# untitled.net
KiCad netlist of a schematic drawn in EAGLE
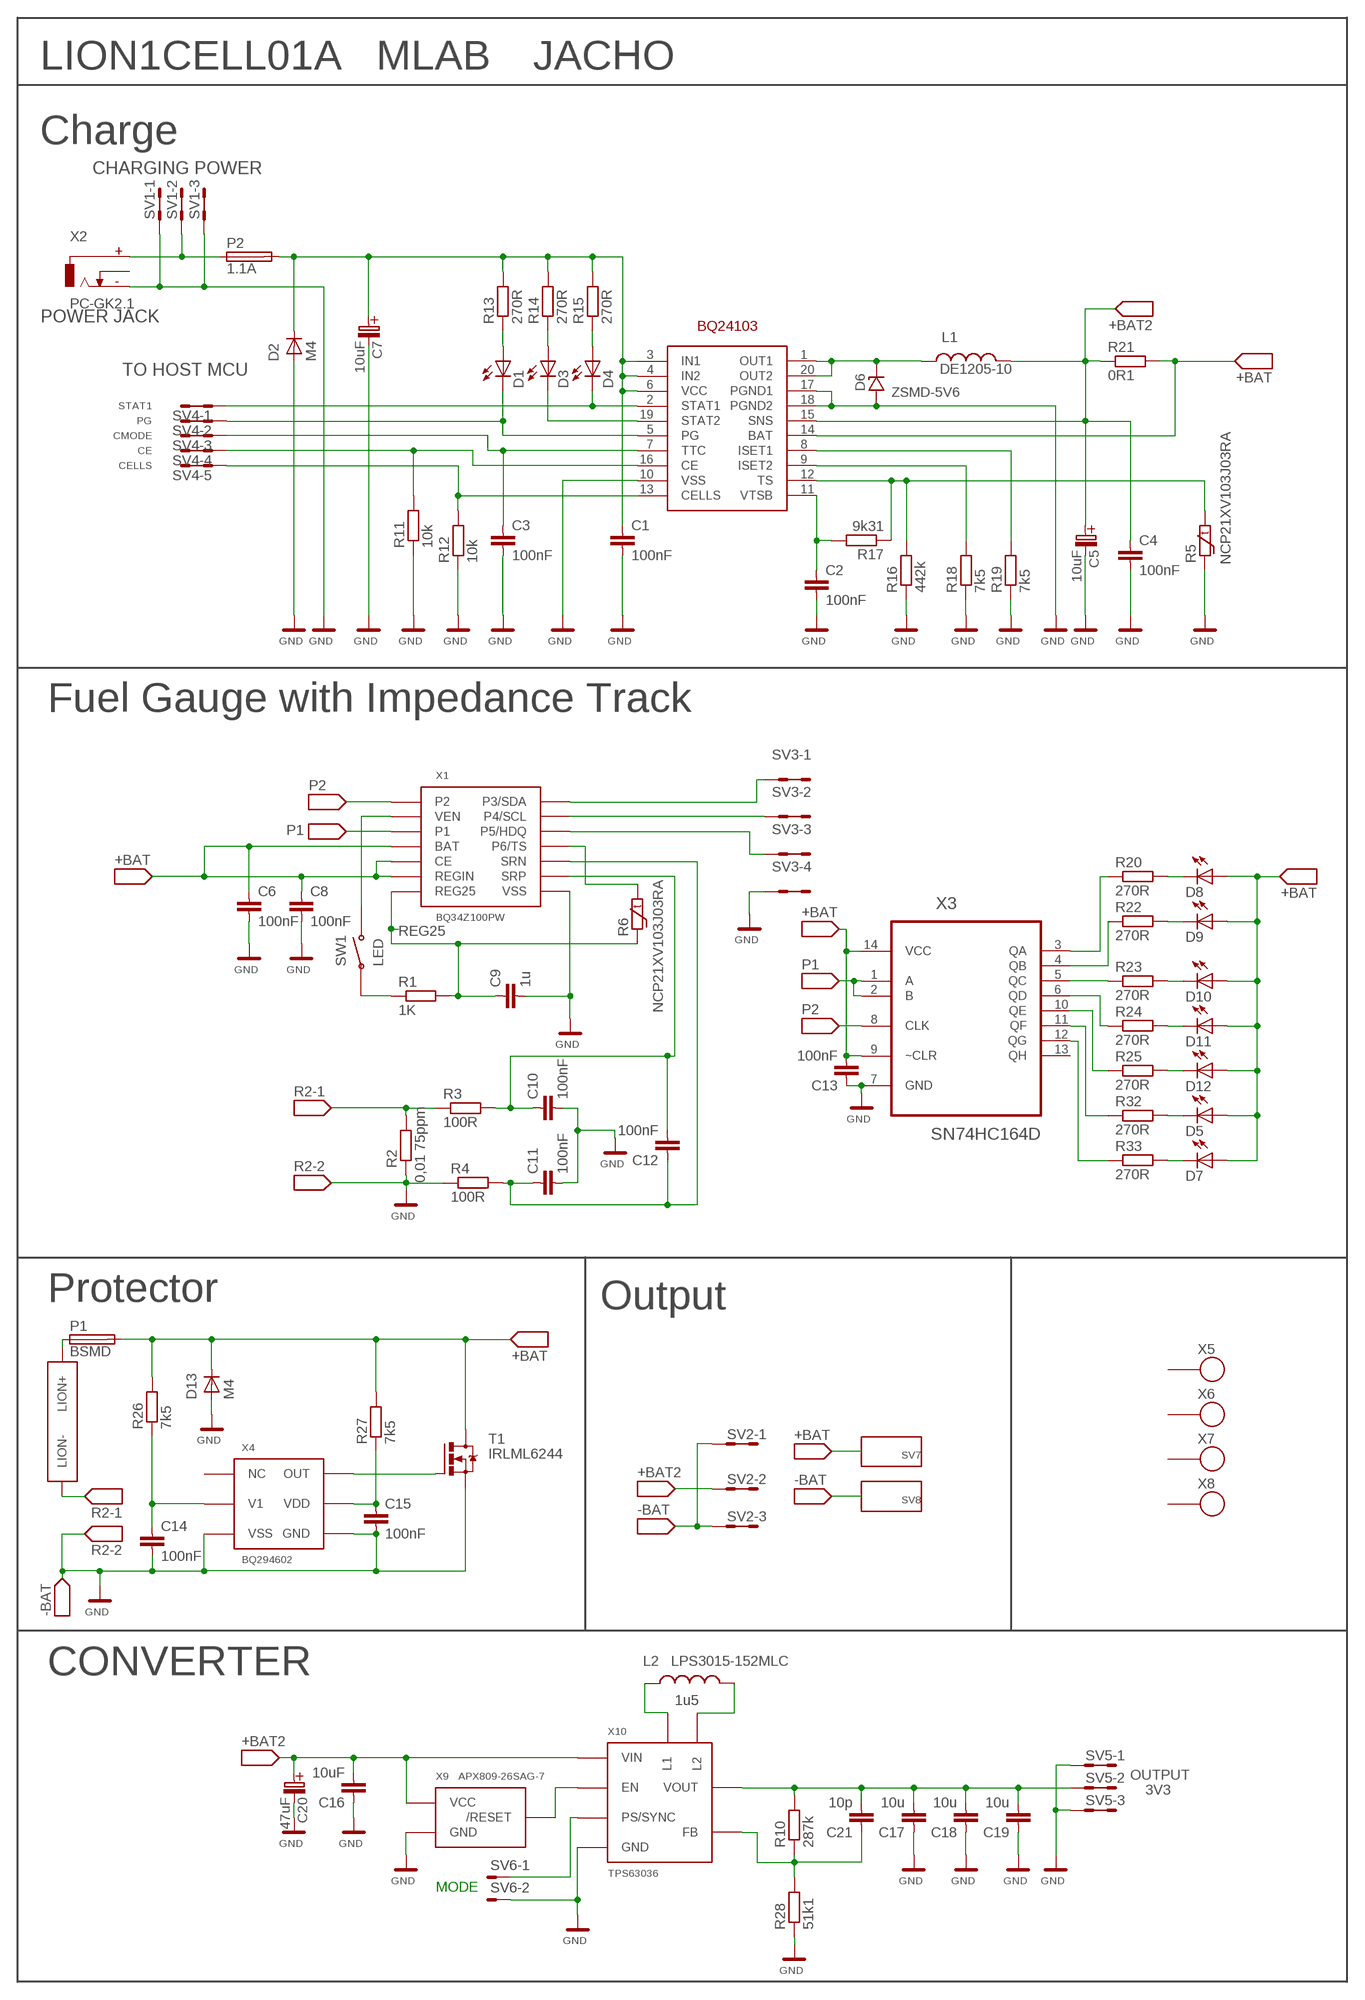
[diagram p0: schematic, sheet 1]

(export (version "E")
  (design (tool "Eeschema 10.0.6"))
  (components
    (comp (ref "C1")
      (value "100nF")
      (footprint "eagle-import:C0805")
      (libsource (lib "eagle-import") (part "C0805"))
    )
    (comp (ref "C2")
      (value "100nF")
      (footprint "eagle-import:C0805")
      (libsource (lib "eagle-import") (part "C0805"))
    )
    (comp (ref "C3")
      (value "100nF")
      (footprint "eagle-import:C0805")
      (libsource (lib "eagle-import") (part "C0805"))
    )
    (comp (ref "C4")
      (value "100nF")
      (footprint "eagle-import:C0805")
      (libsource (lib "eagle-import") (part "C0805"))
    )
    (comp (ref "C5") (value "10uF") (footprint "eagle-import:B") (libsource (lib "eagle-import") (part "B")))
    (comp (ref "C6")
      (value "100nF")
      (footprint "eagle-import:C0805")
      (libsource (lib "eagle-import") (part "C0805"))
    )
    (comp (ref "C7") (value "10uF") (footprint "eagle-import:B") (libsource (lib "eagle-import") (part "B")))
    (comp (ref "C8")
      (value "100nF")
      (footprint "eagle-import:C0805")
      (libsource (lib "eagle-import") (part "C0805"))
    )
    (comp (ref "C9")
      (value "1u")
      (footprint "eagle-import:C0805")
      (libsource (lib "eagle-import") (part "C0805"))
    )
    (comp (ref "C10")
      (value "100nF")
      (footprint "eagle-import:C0805")
      (libsource (lib "eagle-import") (part "C0805"))
    )
    (comp (ref "C11")
      (value "100nF")
      (footprint "eagle-import:C0805")
      (libsource (lib "eagle-import") (part "C0805"))
    )
    (comp (ref "C12")
      (value "100nF")
      (footprint "eagle-import:C0805")
      (libsource (lib "eagle-import") (part "C0805"))
    )
    (comp (ref "C13")
      (value "100nF")
      (footprint "eagle-import:C0805")
      (libsource (lib "eagle-import") (part "C0805"))
    )
    (comp (ref "C14")
      (value "100nF")
      (footprint "eagle-import:C0805")
      (libsource (lib "eagle-import") (part "C0805"))
    )
    (comp (ref "C15")
      (value "100nF")
      (footprint "eagle-import:C0805")
      (libsource (lib "eagle-import") (part "C0805"))
    )
    (comp (ref "C16")
      (value "10uF")
      (footprint "eagle-import:C0805")
      (libsource (lib "eagle-import") (part "C0805"))
    )
    (comp (ref "C17")
      (value "10u")
      (footprint "eagle-import:C0805")
      (libsource (lib "eagle-import") (part "C0805"))
    )
    (comp (ref "C18")
      (value "10u")
      (footprint "eagle-import:C0805")
      (libsource (lib "eagle-import") (part "C0805"))
    )
    (comp (ref "C19")
      (value "10u")
      (footprint "eagle-import:C0805")
      (libsource (lib "eagle-import") (part "C0805"))
    )
    (comp (ref "C20") (value "47uF") (footprint "eagle-import:B") (libsource (lib "eagle-import") (part "B")))
    (comp (ref "C21")
      (value "10p")
      (footprint "eagle-import:0603")
      (libsource (lib "eagle-import") (part "C0603"))
    )
    (comp (ref "D1")
      (value "LED1206_2")
      (footprint "eagle-import:1206_2")
      (libsource (lib "eagle-import") (part "LED1206_2"))
    )
    (comp (ref "D2")
      (value "M4")
      (footprint "eagle-import:SMB")
      (libsource (lib "eagle-import") (part "D-OB."))
    )
    (comp (ref "D3")
      (value "LED1206_2")
      (footprint "eagle-import:1206_2")
      (libsource (lib "eagle-import") (part "LED1206_2"))
    )
    (comp (ref "D4")
      (value "LED1206_2")
      (footprint "eagle-import:1206_2")
      (libsource (lib "eagle-import") (part "LED1206_2"))
    )
    (comp (ref "D5")
      (value "LED1206_2")
      (footprint "eagle-import:1206_2")
      (libsource (lib "eagle-import") (part "LED1206_2"))
    )
    (comp (ref "D6")
      (value "ZSMD-5V6")
      (footprint "eagle-import:MINIMELF")
      (libsource (lib "eagle-import") (part "D-ZENEROVA"))
    )
    (comp (ref "D7")
      (value "LED1206_2")
      (footprint "eagle-import:1206_2")
      (libsource (lib "eagle-import") (part "LED1206_2"))
    )
    (comp (ref "D8")
      (value "LED1206_2")
      (footprint "eagle-import:1206_2")
      (libsource (lib "eagle-import") (part "LED1206_2"))
    )
    (comp (ref "D9")
      (value "LED1206_2")
      (footprint "eagle-import:1206_2")
      (libsource (lib "eagle-import") (part "LED1206_2"))
    )
    (comp (ref "D10")
      (value "LED1206_2")
      (footprint "eagle-import:1206_2")
      (libsource (lib "eagle-import") (part "LED1206_2"))
    )
    (comp (ref "D11")
      (value "LED1206_2")
      (footprint "eagle-import:1206_2")
      (libsource (lib "eagle-import") (part "LED1206_2"))
    )
    (comp (ref "D12")
      (value "LED1206_2")
      (footprint "eagle-import:1206_2")
      (libsource (lib "eagle-import") (part "LED1206_2"))
    )
    (comp (ref "D13")
      (value "M4")
      (footprint "eagle-import:SMA")
      (libsource (lib "eagle-import") (part "D-OB.SMA"))
    )
    (comp (ref "L1")
      (value "DE1205-10")
      (footprint "eagle-import:DE1205-10")
      (libsource (lib "eagle-import") (part "DE1205-10"))
    )
    (comp (ref "L2")
      (value "LPS3015-152MLC")
      (footprint "eagle-import:LPS3015")
      (libsource (lib "eagle-import") (part "LPS3015"))
    )
    (comp (ref "P1")
      (value "BSMD")
      (footprint "eagle-import:2410")
      (libsource (lib "eagle-import") (part "POJISTKA2410"))
    )
    (comp (ref "P2")
      (value "1.1A")
      (footprint "eagle-import:1812")
      (libsource (lib "eagle-import") (part "POJISTKA_1812"))
    )
    (comp (ref "R1")
      (value "1K")
      (footprint "eagle-import:0805")
      (libsource (lib "eagle-import") (part "R0805"))
    )
    (comp (ref "R2")
      (value "0,01 75ppm")
      (footprint "eagle-import:0805")
      (libsource (lib "eagle-import") (part "R0805"))
    )
    (comp (ref "R3")
      (value "100R")
      (footprint "eagle-import:0805")
      (libsource (lib "eagle-import") (part "R0805"))
    )
    (comp (ref "R4")
      (value "100R")
      (footprint "eagle-import:0805")
      (libsource (lib "eagle-import") (part "R0805"))
    )
    (comp (ref "R5")
      (value "NCP21XV103J03RA")
      (footprint "eagle-import:0805")
      (libsource (lib "eagle-import") (part "TERMISTOR0805"))
    )
    (comp (ref "R6")
      (value "NCP21XV103J03RA")
      (footprint "eagle-import:0805")
      (libsource (lib "eagle-import") (part "TERMISTOR0805"))
    )
    (comp (ref "R10")
      (value "287k")
      (footprint "eagle-import:0603")
      (libsource (lib "eagle-import") (part "R0603"))
    )
    (comp (ref "R11")
      (value "10k")
      (footprint "eagle-import:0805")
      (libsource (lib "eagle-import") (part "R0805"))
    )
    (comp (ref "R12")
      (value "10k")
      (footprint "eagle-import:0805")
      (libsource (lib "eagle-import") (part "R0805"))
    )
    (comp (ref "R13")
      (value "270R")
      (footprint "eagle-import:0805")
      (libsource (lib "eagle-import") (part "R0805"))
    )
    (comp (ref "R14")
      (value "270R")
      (footprint "eagle-import:0805")
      (libsource (lib "eagle-import") (part "R0805"))
    )
    (comp (ref "R15")
      (value "270R")
      (footprint "eagle-import:0805")
      (libsource (lib "eagle-import") (part "R0805"))
    )
    (comp (ref "R16")
      (value "442k")
      (footprint "eagle-import:0805")
      (libsource (lib "eagle-import") (part "R0805"))
    )
    (comp (ref "R17")
      (value "9k31")
      (footprint "eagle-import:0805")
      (libsource (lib "eagle-import") (part "R0805"))
    )
    (comp (ref "R18")
      (value "7k5")
      (footprint "eagle-import:0805")
      (libsource (lib "eagle-import") (part "R0805"))
    )
    (comp (ref "R19")
      (value "7k5")
      (footprint "eagle-import:0805")
      (libsource (lib "eagle-import") (part "R0805"))
    )
    (comp (ref "R20")
      (value "270R")
      (footprint "eagle-import:0805")
      (libsource (lib "eagle-import") (part "R0805"))
    )
    (comp (ref "R21")
      (value "0R1")
      (footprint "eagle-import:R2512")
      (libsource (lib "eagle-import") (part "R-EU_R2512"))
    )
    (comp (ref "R22")
      (value "270R")
      (footprint "eagle-import:0805")
      (libsource (lib "eagle-import") (part "R0805"))
    )
    (comp (ref "R23")
      (value "270R")
      (footprint "eagle-import:0805")
      (libsource (lib "eagle-import") (part "R0805"))
    )
    (comp (ref "R24")
      (value "270R")
      (footprint "eagle-import:0805")
      (libsource (lib "eagle-import") (part "R0805"))
    )
    (comp (ref "R25")
      (value "270R")
      (footprint "eagle-import:0805")
      (libsource (lib "eagle-import") (part "R0805"))
    )
    (comp (ref "R26")
      (value "7k5")
      (footprint "eagle-import:0805")
      (libsource (lib "eagle-import") (part "R0805"))
    )
    (comp (ref "R27")
      (value "7k5")
      (footprint "eagle-import:0805")
      (libsource (lib "eagle-import") (part "R0805"))
    )
    (comp (ref "R28")
      (value "51k1")
      (footprint "eagle-import:0603")
      (libsource (lib "eagle-import") (part "R0603"))
    )
    (comp (ref "R32")
      (value "270R")
      (footprint "eagle-import:0805")
      (libsource (lib "eagle-import") (part "R0805"))
    )
    (comp (ref "R33")
      (value "270R")
      (footprint "eagle-import:0805")
      (libsource (lib "eagle-import") (part "R0805"))
    )
    (comp (ref "SV1")
      (value "MA03-2")
      (footprint "eagle-import:MA03-2")
      (libsource (lib "eagle-import") (part "MA03-2"))
    )
    (comp (ref "SV2")
      (value "MA03-2")
      (footprint "eagle-import:MA03-2")
      (libsource (lib "eagle-import") (part "MA03-2"))
    )
    (comp (ref "SV3")
      (value "MA04-2")
      (footprint "eagle-import:MA04-2")
      (libsource (lib "eagle-import") (part "MA04-2"))
    )
    (comp (ref "SV4")
      (value "MA05-2")
      (footprint "eagle-import:MA05-2")
      (libsource (lib "eagle-import") (part "MA05-2"))
    )
    (comp (ref "SV5")
      (value "MA03-2")
      (footprint "eagle-import:MA03-2")
      (libsource (lib "eagle-import") (part "MA03-2"))
    )
    (comp (ref "SV6")
      (value "MA02-1")
      (footprint "eagle-import:MA02-1")
      (libsource (lib "eagle-import") (part "MA02-1"))
    )
    (comp (ref "SV7")
      (value "WAGO256")
      (footprint "eagle-import:WAGO256")
      (libsource (lib "eagle-import") (part "WAGO256"))
    )
    (comp (ref "SV8")
      (value "WAGO256")
      (footprint "eagle-import:WAGO256")
      (libsource (lib "eagle-import") (part "WAGO256"))
    )
    (comp (ref "SW1")
      (value "TACT-64K")
      (footprint "eagle-import:TACT-64K")
      (libsource (lib "eagle-import") (part "TACT-64K"))
    )
    (comp (ref "T1")
      (value "IRLML6244")
      (footprint "eagle-import:SOT23")
      (libsource (lib "eagle-import") (part "IRLML6244TRPBF"))
    )
    (comp (ref "U$2")
      (value "LION1")
      (footprint "eagle-import:LION1")
      (libsource (lib "eagle-import") (part "LION1"))
    )
    (comp (ref "U1")
      (value "BQ24103")
      (footprint "eagle-import:RHL_R-VQFN-N20")
      (libsource (lib "eagle-import") (part "BQ24103"))
    )
    (comp (ref "X1")
      (value "BQ34Z100PW")
      (footprint "eagle-import:TSSOP14")
      (libsource (lib "eagle-import") (part "BQ34Z100PW"))
    )
    (comp (ref "X2")
      (value "DC2.1MM")
      (footprint "eagle-import:DC2.1MM")
      (libsource (lib "eagle-import") (part "DC2.1MM"))
    )
    (comp (ref "X3")
      (value "SN74HC164D")
      (footprint "eagle-import:SOIC127P600X175-14N")
      (libsource (lib "eagle-import") (part "SN74HC164D"))
    )
    (comp (ref "X4")
      (value "BQ294602")
      (footprint "eagle-import:SON_N6")
      (libsource (lib "eagle-import") (part "BQ294602"))
    )
    (comp (ref "X5")
      (value "SROUB3M")
      (footprint "eagle-import:SROUB3M")
      (libsource (lib "eagle-import") (part "SROUB3M"))
    )
    (comp (ref "X6")
      (value "SROUB3M")
      (footprint "eagle-import:SROUB3M")
      (libsource (lib "eagle-import") (part "SROUB3M"))
    )
    (comp (ref "X7")
      (value "SROUB3M")
      (footprint "eagle-import:SROUB3M")
      (libsource (lib "eagle-import") (part "SROUB3M"))
    )
    (comp (ref "X8")
      (value "SROUB3M")
      (footprint "eagle-import:SROUB3M")
      (libsource (lib "eagle-import") (part "SROUB3M"))
    )
    (comp (ref "X9")
      (value "APX809-26SAG-7")
      (footprint "eagle-import:SOT23")
      (libsource (lib "eagle-import") (part "APX809-26SA"))
    )
    (comp (ref "X10")
      (value "TPS63036")
      (footprint "eagle-import:DSBGA8")
      (libsource (lib "eagle-import") (part "TPS63036"))
    )
  )
  (nets
    (net (code "1") (name "/+BAT") (class "Default")
      (node (ref "C13") (pin "2") (pinfunction "2_2") (pintype "passive"))
      (node (ref "C6") (pin "1") (pinfunction "1_1") (pintype "passive"))
      (node (ref "C8") (pin "1") (pinfunction "1_1") (pintype "passive"))
      (node (ref "D10") (pin "A") (pinfunction "A_A") (pintype "passive"))
      (node (ref "D11") (pin "A") (pinfunction "A_A") (pintype "passive"))
      (node (ref "D12") (pin "A") (pinfunction "A_A") (pintype "passive"))
      (node (ref "D13") (pin "K") (pinfunction "C_K") (pintype "passive"))
      (node (ref "D5") (pin "A") (pinfunction "A_A") (pintype "passive"))
      (node (ref "D7") (pin "A") (pinfunction "A_A") (pintype "passive"))
      (node (ref "D8") (pin "A") (pinfunction "A_A") (pintype "passive"))
      (node (ref "D9") (pin "A") (pinfunction "A_A") (pintype "passive"))
      (node (ref "P1") (pin "2") (pinfunction "2_2") (pintype "passive"))
      (node (ref "R21") (pin "2") (pinfunction "2_2") (pintype "passive"))
      (node (ref "R26") (pin "2") (pinfunction "2_2") (pintype "passive"))
      (node (ref "R27") (pin "2") (pinfunction "2_2") (pintype "passive"))
      (node (ref "SV7") (pin "1") (pinfunction "P$1_1") (pintype "passive"))
      (node (ref "SV7") (pin "A1") (pinfunction "P$1_A1") (pintype "passive"))
      (node (ref "T1") (pin "3") (pinfunction "D_3") (pintype "passive"))
      (node (ref "U1") (pin "14") (pinfunction "BAT_14") (pintype "bidirectional"))
      (node (ref "X1") (pin "4") (pinfunction "BAT_4") (pintype "bidirectional"))
      (node (ref "X1") (pin "5") (pinfunction "CE_5") (pintype "bidirectional"))
      (node (ref "X1") (pin "6") (pinfunction "REGIN_6") (pintype "bidirectional"))
      (node (ref "X3") (pin "14") (pinfunction "VCC_14") (pintype "power_in"))
      (node (ref "X3") (pin "9") (pinfunction "~{CLR}_9") (pintype "input"))
    )
    (net (code "2") (name "/+BAT2") (class "Default")
      (node (ref "C16") (pin "2") (pinfunction "2_2") (pintype "passive"))
      (node (ref "C20") (pin "+") (pinfunction "C_EL+_+") (pintype "passive"))
      (node (ref "C4") (pin "1") (pinfunction "1_1") (pintype "passive"))
      (node (ref "C5") (pin "+") (pinfunction "C_EL+_+") (pintype "passive"))
      (node (ref "L1") (pin "P$2") (pinfunction "2_P$2") (pintype "passive"))
      (node (ref "R21") (pin "1") (pinfunction "1_1") (pintype "passive"))
      (node (ref "SV2") (pin "3") (pinfunction "K_3") (pintype "passive"))
      (node (ref "SV2") (pin "4") (pinfunction "K_4") (pintype "passive"))
      (node (ref "U1") (pin "15") (pinfunction "SNS_15") (pintype "bidirectional"))
      (node (ref "X10") (pin "A1") (pinfunction "VIN_A1") (pintype "input"))
      (node (ref "X9") (pin "3") (pinfunction "VCC_3") (pintype "input"))
    )
    (net (code "3") (name "/P1") (class "Default")
      (node (ref "X1") (pin "3") (pinfunction "P1_3") (pintype "bidirectional"))
      (node (ref "X3") (pin "1") (pinfunction "A_1") (pintype "input"))
      (node (ref "X3") (pin "2") (pinfunction "B_2") (pintype "input"))
    )
    (net (code "4") (name "/P2") (class "Default")
      (node (ref "X1") (pin "1") (pinfunction "P2_1") (pintype "bidirectional"))
      (node (ref "X3") (pin "8") (pinfunction "CLK_8") (pintype "input"))
    )
    (net (code "5") (name "/R2") (class "Default")
      (node (ref "R2") (pin "2") (pinfunction "2_2") (pintype "passive"))
      (node (ref "R3") (pin "1") (pinfunction "1_1") (pintype "passive"))
      (node (ref "U$2") (pin "-") (pinfunction "LION-_-") (pintype "bidirectional"))
      (node (ref "U$2") (pin "-1") (pinfunction "LION-_-1") (pintype "bidirectional"))
    )
    (net (code "6") (name "GND") (class "Default")
      (node (ref "C1") (pin "2") (pinfunction "2_2") (pintype "passive"))
      (node (ref "C10") (pin "2") (pinfunction "2_2") (pintype "passive"))
      (node (ref "C11") (pin "2") (pinfunction "2_2") (pintype "passive"))
      (node (ref "C13") (pin "1") (pinfunction "1_1") (pintype "passive"))
      (node (ref "C14") (pin "2") (pinfunction "2_2") (pintype "passive"))
      (node (ref "C15") (pin "2") (pinfunction "2_2") (pintype "passive"))
      (node (ref "C16") (pin "1") (pinfunction "1_1") (pintype "passive"))
      (node (ref "C17") (pin "1") (pinfunction "1_1") (pintype "passive"))
      (node (ref "C18") (pin "1") (pinfunction "1_1") (pintype "passive"))
      (node (ref "C19") (pin "1") (pinfunction "1_1") (pintype "passive"))
      (node (ref "C2") (pin "2") (pinfunction "2_2") (pintype "passive"))
      (node (ref "C20") (pin "-") (pinfunction "C_EL-_-") (pintype "passive"))
      (node (ref "C3") (pin "2") (pinfunction "2_2") (pintype "passive"))
      (node (ref "C4") (pin "2") (pinfunction "2_2") (pintype "passive"))
      (node (ref "C5") (pin "-") (pinfunction "C_EL-_-") (pintype "passive"))
      (node (ref "C6") (pin "2") (pinfunction "2_2") (pintype "passive"))
      (node (ref "C7") (pin "-") (pinfunction "C_EL-_-") (pintype "passive"))
      (node (ref "C8") (pin "2") (pinfunction "2_2") (pintype "passive"))
      (node (ref "C9") (pin "2") (pinfunction "2_2") (pintype "passive"))
      (node (ref "D13") (pin "A") (pinfunction "A_A") (pintype "passive"))
      (node (ref "D2") (pin "A") (pinfunction "A_A") (pintype "passive"))
      (node (ref "D6") (pin "A") (pinfunction "A_A") (pintype "passive"))
      (node (ref "R11") (pin "1") (pinfunction "1_1") (pintype "passive"))
      (node (ref "R12") (pin "1") (pinfunction "1_1") (pintype "passive"))
      (node (ref "R16") (pin "1") (pinfunction "1_1") (pintype "passive"))
      (node (ref "R18") (pin "1") (pinfunction "1_1") (pintype "passive"))
      (node (ref "R19") (pin "1") (pinfunction "1_1") (pintype "passive"))
      (node (ref "R2") (pin "1") (pinfunction "1_1") (pintype "passive"))
      (node (ref "R28") (pin "1") (pinfunction "1_1") (pintype "passive"))
      (node (ref "R4") (pin "1") (pinfunction "1_1") (pintype "passive"))
      (node (ref "R5") (pin "1") (pinfunction "1_1") (pintype "passive"))
      (node (ref "SV1") (pin "1") (pinfunction "K_1") (pintype "passive"))
      (node (ref "SV1") (pin "2") (pinfunction "K_2") (pintype "passive"))
      (node (ref "SV1") (pin "5") (pinfunction "K_5") (pintype "passive"))
      (node (ref "SV1") (pin "6") (pinfunction "K_6") (pintype "passive"))
      (node (ref "SV2") (pin "1") (pinfunction "K_1") (pintype "passive"))
      (node (ref "SV2") (pin "2") (pinfunction "K_2") (pintype "passive"))
      (node (ref "SV2") (pin "5") (pinfunction "K_5") (pintype "passive"))
      (node (ref "SV2") (pin "6") (pinfunction "K_6") (pintype "passive"))
      (node (ref "SV3") (pin "7") (pinfunction "K_7") (pintype "passive"))
      (node (ref "SV3") (pin "8") (pinfunction "K_8") (pintype "passive"))
      (node (ref "SV5") (pin "1") (pinfunction "K_1") (pintype "passive"))
      (node (ref "SV5") (pin "2") (pinfunction "K_2") (pintype "passive"))
      (node (ref "SV5") (pin "5") (pinfunction "K_5") (pintype "passive"))
      (node (ref "SV5") (pin "6") (pinfunction "K_6") (pintype "passive"))
      (node (ref "SV6") (pin "2") (pinfunction "P$1_2") (pintype "passive"))
      (node (ref "SV8") (pin "1") (pinfunction "P$1_1") (pintype "passive"))
      (node (ref "SV8") (pin "A1") (pinfunction "P$1_A1") (pintype "passive"))
      (node (ref "T1") (pin "2") (pinfunction "S_2") (pintype "passive"))
      (node (ref "U1") (pin "10") (pinfunction "VSS_10") (pintype "bidirectional"))
      (node (ref "U1") (pin "17") (pinfunction "PGND1_17") (pintype "bidirectional"))
      (node (ref "U1") (pin "18") (pinfunction "PGND2_18") (pintype "bidirectional"))
      (node (ref "X1") (pin "8") (pinfunction "VSS_8") (pintype "bidirectional"))
      (node (ref "X10") (pin "C2") (pinfunction "GND_C2") (pintype "passive"))
      (node (ref "X2") (pin "GND") (pinfunction "-_GND") (pintype "passive"))
      (node (ref "X3") (pin "7") (pinfunction "GND_7") (pintype "passive"))
      (node (ref "X4") (pin "3") (pinfunction "VSS_3") (pintype "bidirectional"))
      (node (ref "X4") (pin "4") (pinfunction "VSS_4") (pintype "bidirectional"))
      (node (ref "X4") (pin "7") (pinfunction "GND_7") (pintype "bidirectional"))
      (node (ref "X9") (pin "1") (pinfunction "GND_1") (pintype "passive"))
    )
    (net (code "7") (name "Net-(C7-C_EL+)") (class "Default")
      (node (ref "C1") (pin "1") (pinfunction "1_1") (pintype "passive"))
      (node (ref "C7") (pin "+") (pinfunction "C_EL+_+") (pintype "passive"))
      (node (ref "D2") (pin "K") (pinfunction "C_K") (pintype "passive"))
      (node (ref "P2") (pin "2") (pinfunction "2_2") (pintype "passive"))
      (node (ref "R13") (pin "2") (pinfunction "2_2") (pintype "passive"))
      (node (ref "R14") (pin "2") (pinfunction "2_2") (pintype "passive"))
      (node (ref "R15") (pin "2") (pinfunction "2_2") (pintype "passive"))
      (node (ref "U1") (pin "3") (pinfunction "IN1_3") (pintype "bidirectional"))
      (node (ref "U1") (pin "4") (pinfunction "IN2_4") (pintype "bidirectional"))
      (node (ref "U1") (pin "6") (pinfunction "VCC_6") (pintype "bidirectional"))
    )
    (net (code "8") (name "Net-(D1-C)") (class "Default")
      (node (ref "D1") (pin "K") (pinfunction "C_K") (pintype "passive"))
      (node (ref "SV4") (pin "3") (pinfunction "K_3") (pintype "passive"))
      (node (ref "SV4") (pin "4") (pinfunction "K_4") (pintype "passive"))
      (node (ref "U1") (pin "5") (pinfunction "PG_5") (pintype "bidirectional"))
    )
    (net (code "9") (name "Net-(D1-PadA)") (class "Default")
      (node (ref "D1") (pin "A") (pinfunction "A_A") (pintype "passive"))
      (node (ref "R13") (pin "1") (pinfunction "1_1") (pintype "passive"))
    )
    (net (code "10") (name "Net-(D3-C)") (class "Default")
      (node (ref "D3") (pin "K") (pinfunction "C_K") (pintype "passive"))
      (node (ref "U1") (pin "19") (pinfunction "STAT2_19") (pintype "bidirectional"))
    )
    (net (code "11") (name "Net-(D3-PadA)") (class "Default")
      (node (ref "D3") (pin "A") (pinfunction "A_A") (pintype "passive"))
      (node (ref "R14") (pin "1") (pinfunction "1_1") (pintype "passive"))
    )
    (net (code "12") (name "Net-(D4-C)") (class "Default")
      (node (ref "D4") (pin "K") (pinfunction "C_K") (pintype "passive"))
      (node (ref "SV4") (pin "1") (pinfunction "K_1") (pintype "passive"))
      (node (ref "SV4") (pin "2") (pinfunction "K_2") (pintype "passive"))
      (node (ref "U1") (pin "2") (pinfunction "STAT1_2") (pintype "bidirectional"))
    )
    (net (code "13") (name "Net-(D4-PadA)") (class "Default")
      (node (ref "D4") (pin "A") (pinfunction "A_A") (pintype "passive"))
      (node (ref "R15") (pin "1") (pinfunction "1_1") (pintype "passive"))
    )
    (net (code "14") (name "Net-(D5-C)") (class "Default")
      (node (ref "D5") (pin "K") (pinfunction "C_K") (pintype "passive"))
      (node (ref "R32") (pin "2") (pinfunction "2_2") (pintype "passive"))
    )
    (net (code "15") (name "Net-(D6-K)") (class "Default")
      (node (ref "D6") (pin "C") (pinfunction "K_C") (pintype "passive"))
      (node (ref "L1") (pin "P$1") (pinfunction "1_P$1") (pintype "passive"))
      (node (ref "U1") (pin "1") (pinfunction "OUT1_1") (pintype "bidirectional"))
      (node (ref "U1") (pin "20") (pinfunction "OUT2_20") (pintype "bidirectional"))
    )
    (net (code "16") (name "Net-(D7-C)") (class "Default")
      (node (ref "D7") (pin "K") (pinfunction "C_K") (pintype "passive"))
      (node (ref "R33") (pin "2") (pinfunction "2_2") (pintype "passive"))
    )
    (net (code "17") (name "Net-(D8-C)") (class "Default")
      (node (ref "D8") (pin "K") (pinfunction "C_K") (pintype "passive"))
      (node (ref "R20") (pin "2") (pinfunction "2_2") (pintype "passive"))
    )
    (net (code "18") (name "Net-(D9-C)") (class "Default")
      (node (ref "D9") (pin "K") (pinfunction "C_K") (pintype "passive"))
      (node (ref "R22") (pin "2") (pinfunction "2_2") (pintype "passive"))
    )
    (net (code "19") (name "Net-(D10-C)") (class "Default")
      (node (ref "D10") (pin "K") (pinfunction "C_K") (pintype "passive"))
      (node (ref "R23") (pin "2") (pinfunction "2_2") (pintype "passive"))
    )
    (net (code "20") (name "Net-(D11-C)") (class "Default")
      (node (ref "D11") (pin "K") (pinfunction "C_K") (pintype "passive"))
      (node (ref "R24") (pin "2") (pinfunction "2_2") (pintype "passive"))
    )
    (net (code "21") (name "Net-(D12-C)") (class "Default")
      (node (ref "D12") (pin "K") (pinfunction "C_K") (pintype "passive"))
      (node (ref "R25") (pin "2") (pinfunction "2_2") (pintype "passive"))
    )
    (net (code "22") (name "Net-(P1-Pad1)") (class "Default")
      (node (ref "P1") (pin "1") (pinfunction "1_1") (pintype "passive"))
      (node (ref "U$2") (pin "+") (pinfunction "LION+_+") (pintype "bidirectional"))
      (node (ref "U$2") (pin "+1") (pinfunction "LION+_+1") (pintype "bidirectional"))
    )
    (net (code "23") (name "Net-(P2-Pad1)") (class "Default")
      (node (ref "P2") (pin "1") (pinfunction "1_1") (pintype "passive"))
      (node (ref "SV1") (pin "3") (pinfunction "K_3") (pintype "passive"))
      (node (ref "SV1") (pin "4") (pinfunction "K_4") (pintype "passive"))
      (node (ref "X2") (pin "+") (pinfunction "+_+") (pintype "passive"))
    )
    (net (code "24") (name "Net-(R1-Pad1)") (class "Default")
      (node (ref "R1") (pin "1") (pinfunction "1_1") (pintype "passive"))
      (node (ref "SW1") (pin "P$1") (pinfunction "P$1_P$1") (pintype "passive"))
      (node (ref "SW1") (pin "P$2") (pinfunction "P$1_P$2") (pintype "passive"))
    )
    (net (code "25") (name "Net-(SV6A-P$1)") (class "Default")
      (node (ref "SV6") (pin "1") (pinfunction "P$1_1") (pintype "passive"))
      (node (ref "X10") (pin "B2") (pinfunction "PS/SYNC_B2") (pintype "input"))
    )
    (net (code "26") (name "Net-(T1-G)") (class "Default")
      (node (ref "T1") (pin "1") (pinfunction "G_1") (pintype "passive"))
      (node (ref "X4") (pin "6") (pinfunction "OUT_6") (pintype "bidirectional"))
    )
    (net (code "27") (name "Net-(U1-CE)") (class "Default")
      (node (ref "R11") (pin "2") (pinfunction "2_2") (pintype "passive"))
      (node (ref "SV4") (pin "7") (pinfunction "K_7") (pintype "passive"))
      (node (ref "SV4") (pin "8") (pinfunction "K_8") (pintype "passive"))
      (node (ref "U1") (pin "16") (pinfunction "CE_16") (pintype "bidirectional"))
    )
    (net (code "28") (name "Net-(U1-CELLS)") (class "Default")
      (node (ref "R12") (pin "2") (pinfunction "2_2") (pintype "passive"))
      (node (ref "SV4") (pin "10") (pinfunction "K_10") (pintype "passive"))
      (node (ref "SV4") (pin "9") (pinfunction "K_9") (pintype "passive"))
      (node (ref "U1") (pin "13") (pinfunction "CELLS_13") (pintype "bidirectional"))
    )
    (net (code "29") (name "Net-(U1-ISET1)") (class "Default")
      (node (ref "R19") (pin "2") (pinfunction "2_2") (pintype "passive"))
      (node (ref "U1") (pin "8") (pinfunction "ISET1_8") (pintype "bidirectional"))
    )
    (net (code "30") (name "Net-(U1-ISET2)") (class "Default")
      (node (ref "R18") (pin "2") (pinfunction "2_2") (pintype "passive"))
      (node (ref "U1") (pin "9") (pinfunction "ISET2_9") (pintype "bidirectional"))
    )
    (net (code "31") (name "Net-(U1-TS)") (class "Default")
      (node (ref "R16") (pin "2") (pinfunction "2_2") (pintype "passive"))
      (node (ref "R17") (pin "1") (pinfunction "1_1") (pintype "passive"))
      (node (ref "R5") (pin "2") (pinfunction "2_2") (pintype "passive"))
      (node (ref "U1") (pin "12") (pinfunction "TS_12") (pintype "bidirectional"))
    )
    (net (code "32") (name "Net-(U1-TTC)") (class "Default")
      (node (ref "C3") (pin "1") (pinfunction "1_1") (pintype "passive"))
      (node (ref "SV4") (pin "5") (pinfunction "K_5") (pintype "passive"))
      (node (ref "SV4") (pin "6") (pinfunction "K_6") (pintype "passive"))
      (node (ref "U1") (pin "7") (pinfunction "TTC_7") (pintype "bidirectional"))
    )
    (net (code "33") (name "Net-(U1-VTSB)") (class "Default")
      (node (ref "C2") (pin "1") (pinfunction "1_1") (pintype "passive"))
      (node (ref "R17") (pin "2") (pinfunction "2_2") (pintype "passive"))
      (node (ref "U1") (pin "11") (pinfunction "VTSB_11") (pintype "bidirectional"))
    )
    (net (code "34") (name "Net-(X1-P3{slash}SDA)") (class "Default")
      (node (ref "SV3") (pin "1") (pinfunction "K_1") (pintype "passive"))
      (node (ref "SV3") (pin "2") (pinfunction "K_2") (pintype "passive"))
      (node (ref "X1") (pin "14") (pinfunction "P3/SDA_14") (pintype "bidirectional"))
    )
    (net (code "35") (name "Net-(X1-P4{slash}SCL)") (class "Default")
      (node (ref "SV3") (pin "3") (pinfunction "K_3") (pintype "passive"))
      (node (ref "SV3") (pin "4") (pinfunction "K_4") (pintype "passive"))
      (node (ref "X1") (pin "13") (pinfunction "P4/SCL_13") (pintype "bidirectional"))
    )
    (net (code "36") (name "Net-(X1-P5{slash}HDQ)") (class "Default")
      (node (ref "SV3") (pin "5") (pinfunction "K_5") (pintype "passive"))
      (node (ref "SV3") (pin "6") (pinfunction "K_6") (pintype "passive"))
      (node (ref "X1") (pin "12") (pinfunction "P5/HDQ_12") (pintype "bidirectional"))
    )
    (net (code "37") (name "Net-(X1-P6{slash}TS)") (class "Default")
      (node (ref "R6") (pin "2") (pinfunction "2_2") (pintype "passive"))
      (node (ref "X1") (pin "11") (pinfunction "P6/TS_11") (pintype "bidirectional"))
    )
    (net (code "38") (name "Net-(X1-REG25)") (class "Default")
      (node (ref "C9") (pin "1") (pinfunction "1_1") (pintype "passive"))
      (node (ref "R1") (pin "2") (pinfunction "2_2") (pintype "passive"))
      (node (ref "R6") (pin "1") (pinfunction "1_1") (pintype "passive"))
      (node (ref "X1") (pin "7") (pinfunction "REG25_7") (pintype "bidirectional"))
    )
    (net (code "39") (name "Net-(X1-SRN)") (class "Default")
      (node (ref "C11") (pin "1") (pinfunction "1_1") (pintype "passive"))
      (node (ref "C12") (pin "1") (pinfunction "1_1") (pintype "passive"))
      (node (ref "R4") (pin "2") (pinfunction "2_2") (pintype "passive"))
      (node (ref "X1") (pin "10") (pinfunction "SRN_10") (pintype "bidirectional"))
    )
    (net (code "40") (name "Net-(X1-SRP)") (class "Default")
      (node (ref "C10") (pin "1") (pinfunction "1_1") (pintype "passive"))
      (node (ref "C12") (pin "2") (pinfunction "2_2") (pintype "passive"))
      (node (ref "R3") (pin "2") (pinfunction "2_2") (pintype "passive"))
      (node (ref "X1") (pin "9") (pinfunction "SRP_9") (pintype "bidirectional"))
    )
    (net (code "41") (name "Net-(X1-VEN)") (class "Default")
      (node (ref "SW1") (pin "P$3") (pinfunction "P$2_P$3") (pintype "passive"))
      (node (ref "SW1") (pin "P$4") (pinfunction "P$2_P$4") (pintype "passive"))
      (node (ref "X1") (pin "2") (pinfunction "VEN_2") (pintype "bidirectional"))
    )
    (net (code "42") (name "Net-(X3-QA)") (class "Default")
      (node (ref "R20") (pin "1") (pinfunction "1_1") (pintype "passive"))
      (node (ref "X3") (pin "3") (pinfunction "QA_3") (pintype "output"))
    )
    (net (code "43") (name "Net-(X3-QB)") (class "Default")
      (node (ref "R22") (pin "1") (pinfunction "1_1") (pintype "passive"))
      (node (ref "X3") (pin "4") (pinfunction "QB_4") (pintype "output"))
    )
    (net (code "44") (name "Net-(X3-QC)") (class "Default")
      (node (ref "R23") (pin "1") (pinfunction "1_1") (pintype "passive"))
      (node (ref "X3") (pin "5") (pinfunction "QC_5") (pintype "output"))
    )
    (net (code "45") (name "Net-(X3-QD)") (class "Default")
      (node (ref "R24") (pin "1") (pinfunction "1_1") (pintype "passive"))
      (node (ref "X3") (pin "6") (pinfunction "QD_6") (pintype "output"))
    )
    (net (code "46") (name "Net-(X3-QE)") (class "Default")
      (node (ref "R25") (pin "1") (pinfunction "1_1") (pintype "passive"))
      (node (ref "X3") (pin "10") (pinfunction "QE_10") (pintype "output"))
    )
    (net (code "47") (name "Net-(X3-QF)") (class "Default")
      (node (ref "R32") (pin "1") (pinfunction "1_1") (pintype "passive"))
      (node (ref "X3") (pin "11") (pinfunction "QF_11") (pintype "output"))
    )
    (net (code "48") (name "Net-(X3-QG)") (class "Default")
      (node (ref "R33") (pin "1") (pinfunction "1_1") (pintype "passive"))
      (node (ref "X3") (pin "12") (pinfunction "QG_12") (pintype "output"))
    )
    (net (code "49") (name "Net-(X4-V1)") (class "Default")
      (node (ref "C14") (pin "1") (pinfunction "1_1") (pintype "passive"))
      (node (ref "R26") (pin "1") (pinfunction "1_1") (pintype "passive"))
      (node (ref "X4") (pin "2") (pinfunction "V1_2") (pintype "bidirectional"))
    )
    (net (code "50") (name "Net-(X4-VDD)") (class "Default")
      (node (ref "C15") (pin "1") (pinfunction "1_1") (pintype "passive"))
      (node (ref "R27") (pin "1") (pinfunction "1_1") (pintype "passive"))
      (node (ref "X4") (pin "5") (pinfunction "VDD_5") (pintype "bidirectional"))
    )
    (net (code "51") (name "Net-(X10-EN)") (class "Default")
      (node (ref "X10") (pin "A2") (pinfunction "EN_A2") (pintype "input"))
      (node (ref "X9") (pin "2") (pinfunction "/RESET_2") (pintype "passive"))
    )
    (net (code "52") (name "Net-(X10-FB)") (class "Default")
      (node (ref "C21") (pin "1") (pinfunction "1_1") (pintype "passive"))
      (node (ref "R10") (pin "1") (pinfunction "1_1") (pintype "passive"))
      (node (ref "R28") (pin "2") (pinfunction "2_2") (pintype "passive"))
      (node (ref "X10") (pin "D2") (pinfunction "FB_D2") (pintype "input"))
    )
    (net (code "53") (name "Net-(X10-L1)") (class "Default")
      (node (ref "L2") (pin "1-1") (pinfunction "1_1-1") (pintype "passive"))
      (node (ref "L2") (pin "1-2") (pinfunction "1_1-2") (pintype "passive"))
      (node (ref "L2") (pin "1-3") (pinfunction "1_1-3") (pintype "passive"))
      (node (ref "X10") (pin "B1") (pinfunction "L1_B1") (pintype "passive"))
    )
    (net (code "54") (name "Net-(X10-L2)") (class "Default")
      (node (ref "L2") (pin "2-1") (pinfunction "2_2-1") (pintype "passive"))
      (node (ref "L2") (pin "2-2") (pinfunction "2_2-2") (pintype "passive"))
      (node (ref "L2") (pin "2-3") (pinfunction "2_2-3") (pintype "passive"))
      (node (ref "X10") (pin "C1") (pinfunction "L2_C1") (pintype "passive"))
    )
    (net (code "55") (name "Net-(X10-VOUT)") (class "Default")
      (node (ref "C17") (pin "2") (pinfunction "2_2") (pintype "passive"))
      (node (ref "C18") (pin "2") (pinfunction "2_2") (pintype "passive"))
      (node (ref "C19") (pin "2") (pinfunction "2_2") (pintype "passive"))
      (node (ref "C21") (pin "2") (pinfunction "2_2") (pintype "passive"))
      (node (ref "R10") (pin "2") (pinfunction "2_2") (pintype "passive"))
      (node (ref "SV5") (pin "3") (pinfunction "K_3") (pintype "passive"))
      (node (ref "SV5") (pin "4") (pinfunction "K_4") (pintype "passive"))
      (node (ref "X10") (pin "D1") (pinfunction "VOUT_D1") (pintype "output"))
    )
    (net (code "56") (name "unconnected-(X2-PadSW)") (class "Default")
      (node (ref "X2") (pin "SW") (pinfunction "SW_SW") (pintype "passive"))
    )
    (net (code "57") (name "unconnected-(X3-QH-Pad13)") (class "Default")
      (node (ref "X3") (pin "13") (pinfunction "QH_13") (pintype "output"))
    )
    (net (code "58") (name "unconnected-(X4-NC-Pad1)") (class "Default")
      (node (ref "X4") (pin "1") (pinfunction "NC_1") (pintype "bidirectional"))
    )
    (net (code "59") (name "unconnected-(X5-PadP$1)") (class "Default")
      (node (ref "X5") (pin "P$1") (pinfunction "P$1_P$1") (pintype "bidirectional"))
    )
    (net (code "60") (name "unconnected-(X6-PadP$1)") (class "Default")
      (node (ref "X6") (pin "P$1") (pinfunction "P$1_P$1") (pintype "bidirectional"))
    )
    (net (code "61") (name "unconnected-(X7-PadP$1)") (class "Default")
      (node (ref "X7") (pin "P$1") (pinfunction "P$1_P$1") (pintype "bidirectional"))
    )
    (net (code "62") (name "unconnected-(X8-PadP$1)") (class "Default")
      (node (ref "X8") (pin "P$1") (pinfunction "P$1_P$1") (pintype "bidirectional"))
    )
  )
)
